# Current_sens.net
KiCad netlist of a schematic drawn in Altium Designer
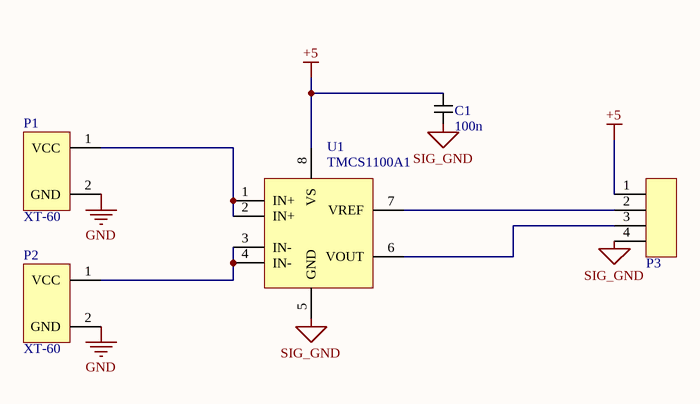
[diagram p0: Current_sens.SchDoc]

(export (version "E")
  (design (tool "Eeschema 10.0.6"))
  (components
    (comp (ref "C1")
      (value "100n")
      (footprint "C_SMD_0805_pcb")
      (fields (field (name "Comment") "SMD"))
      (libsource (lib "FF_component_lib") (part "C_SMD_0805"))
    )
    (comp (ref "P1") (value "XT-60") (footprint "XT-60") (libsource (lib "FF_component_lib") (part "XT-60")))
    (comp (ref "P2") (value "XT-60") (footprint "XT-60") (libsource (lib "FF_component_lib") (part "XT-60")))
    (comp (ref "P3")
      (value "JST_SE_4PIN")
      (footprint "JST_SE_4PIN")
      (libsource (lib "FF_component_lib") (part "JST_SE_4PIN"))
    )
    (comp (ref "U1")
      (value "TMSC1100A1")
      (footprint "SOIC-8")
      (fields (field (name "PART_NAME") "TMCS1100A1"))
      (libsource (lib "FF_component_lib") (part "TMSC1100A1"))
    )
  )
  (nets
    (net (code "1") (name "+5") (class "Default")
      (node (ref "C1") (pin "1") (pinfunction "1_1") (pintype "passive"))
      (node (ref "P3") (pin "1") (pinfunction "1_1") (pintype "passive"))
      (node (ref "U1") (pin "8") (pinfunction "VS_8") (pintype "passive"))
    )
    (net (code "2") (name "GND") (class "Default")
      (node (ref "P1") (pin "2") (pinfunction "GND_2") (pintype "passive"))
      (node (ref "P2") (pin "2") (pinfunction "GND_2") (pintype "passive"))
    )
    (net (code "3") (name "Net-(P1-VCC)") (class "Default")
      (node (ref "P1") (pin "1") (pinfunction "VCC_1") (pintype "passive"))
      (node (ref "U1") (pin "1") (pinfunction "IN+_1") (pintype "passive"))
      (node (ref "U1") (pin "2") (pinfunction "IN+_2") (pintype "passive"))
    )
    (net (code "4") (name "Net-(P2-VCC)") (class "Default")
      (node (ref "P2") (pin "1") (pinfunction "VCC_1") (pintype "passive"))
      (node (ref "U1") (pin "3") (pinfunction "IN-_3") (pintype "passive"))
      (node (ref "U1") (pin "4") (pinfunction "IN-_4") (pintype "passive"))
    )
    (net (code "5") (name "Net-(U1-VOUT)") (class "Default")
      (node (ref "P3") (pin "3") (pinfunction "3_3") (pintype "passive"))
      (node (ref "U1") (pin "6") (pinfunction "VOUT_6") (pintype "passive"))
    )
    (net (code "6") (name "Net-(U1-VREF)") (class "Default")
      (node (ref "P3") (pin "2") (pinfunction "2_2") (pintype "passive"))
      (node (ref "U1") (pin "7") (pinfunction "VREF_7") (pintype "passive"))
    )
    (net (code "7") (name "SIG_GND") (class "Default")
      (node (ref "C1") (pin "2") (pinfunction "2_2") (pintype "passive"))
      (node (ref "P3") (pin "4") (pinfunction "4_4") (pintype "passive"))
      (node (ref "U1") (pin "5") (pinfunction "GND_5") (pintype "passive"))
    )
  )
)
